# auxDaqUnitTopDigital2022_-_2.net
KiCad netlist of a schematic drawn in EAGLE
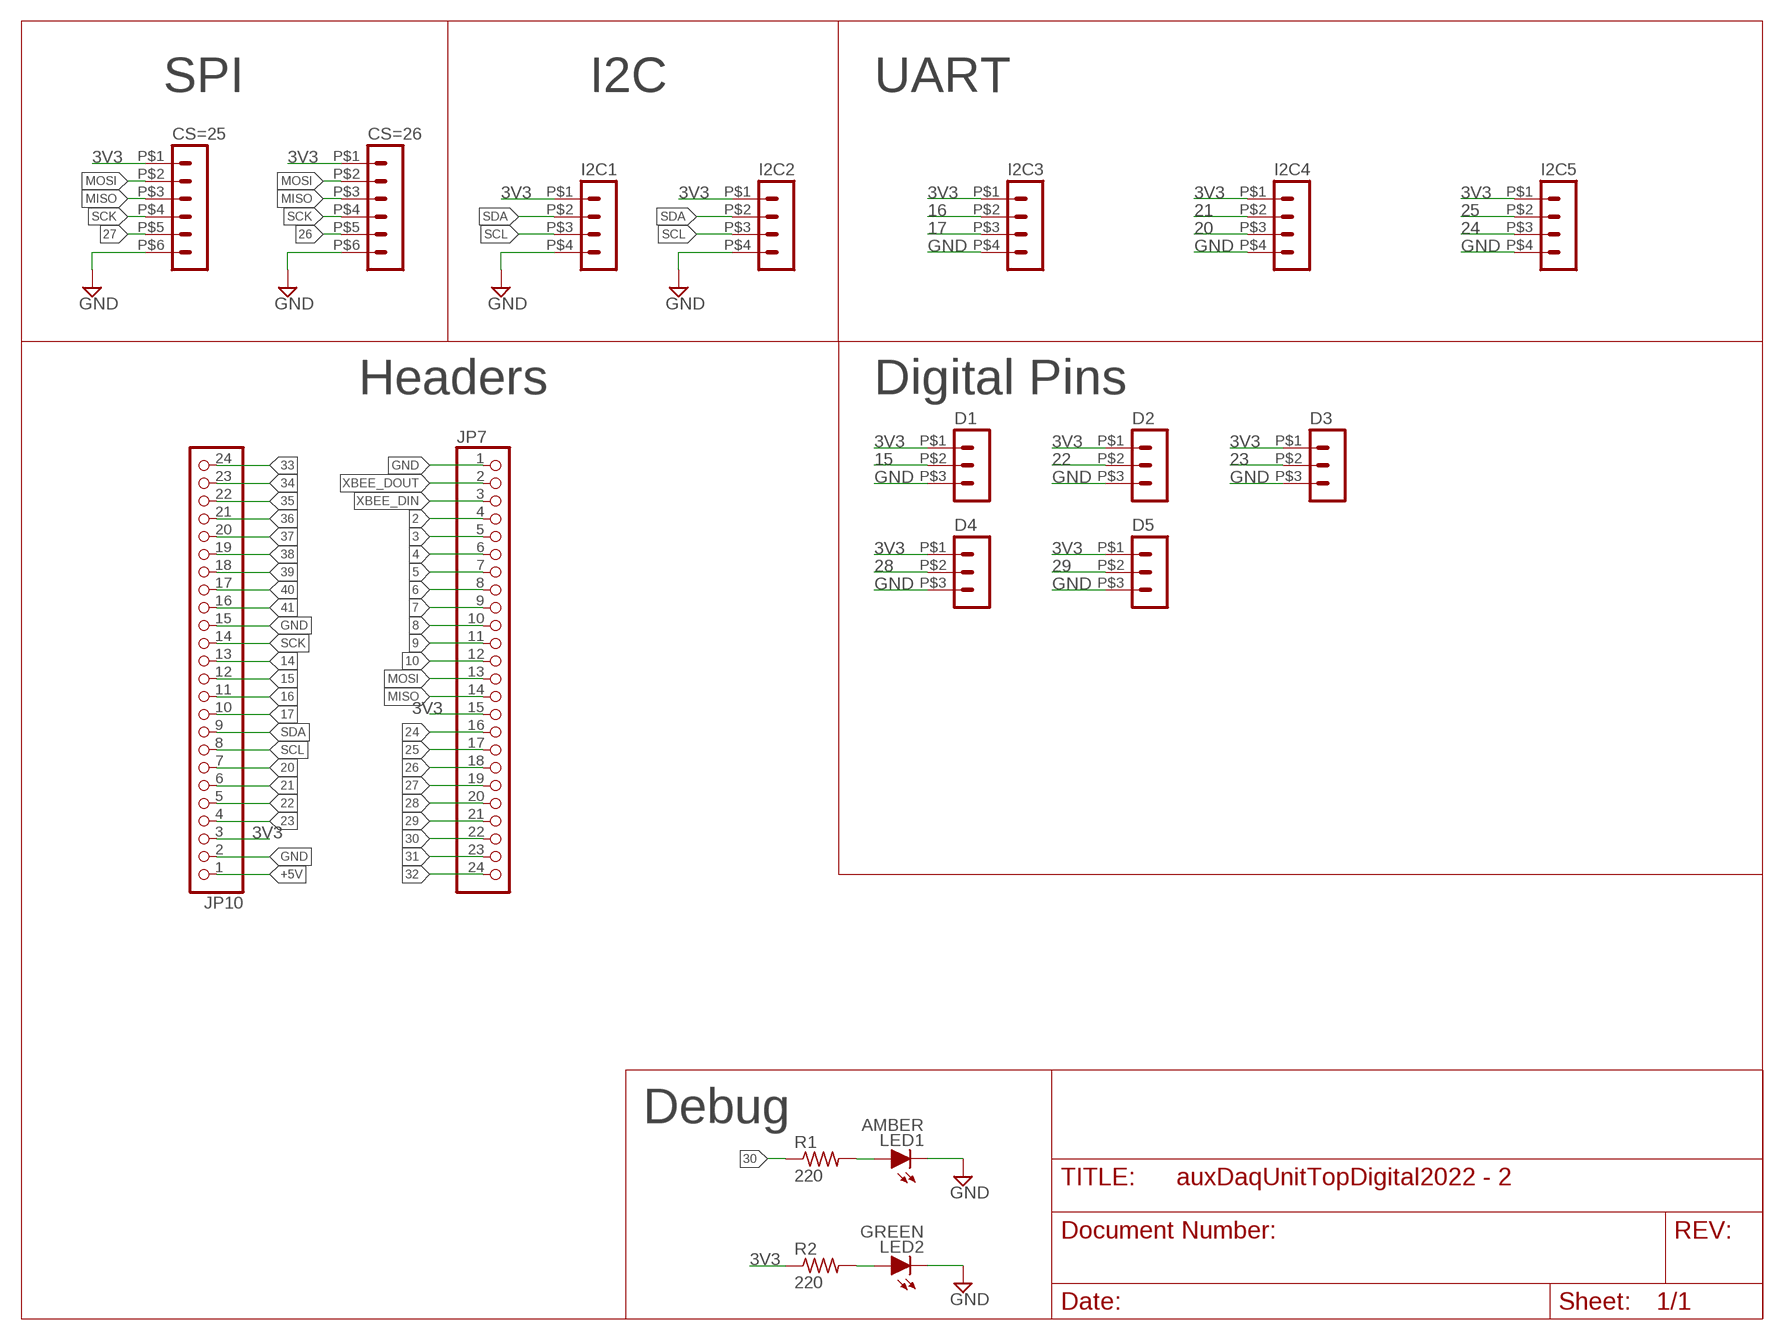
[diagram p0: schematic, sheet 1]

(export (version "E")
  (design (tool "Eeschema 10.0.6"))
  (components
    (comp (ref "CS=25")
      (value "HEADER_POS6_43045-0600")
      (footprint "eagle-import:43045-0600")
      (libsource (lib "eagle-import") (part "HEADER_POS6_?43045-0600"))
    )
    (comp (ref "CS=26")
      (value "HEADER_POS6_43045-0600")
      (footprint "eagle-import:43045-0600")
      (libsource (lib "eagle-import") (part "HEADER_POS6_?43045-0600"))
    )
    (comp (ref "D1")
      (value "HEADER_POS3_43650-0300")
      (footprint "eagle-import:43650-0300")
      (libsource (lib "eagle-import") (part "HEADER_POS3_?43650-0300"))
    )
    (comp (ref "D2")
      (value "HEADER_POS3_43650-0300")
      (footprint "eagle-import:43650-0300")
      (libsource (lib "eagle-import") (part "HEADER_POS3_?43650-0300"))
    )
    (comp (ref "D3")
      (value "HEADER_POS3_43650-0300")
      (footprint "eagle-import:43650-0300")
      (libsource (lib "eagle-import") (part "HEADER_POS3_?43650-0300"))
    )
    (comp (ref "D4")
      (value "HEADER_POS3_43650-0300")
      (footprint "eagle-import:43650-0300")
      (libsource (lib "eagle-import") (part "HEADER_POS3_?43650-0300"))
    )
    (comp (ref "D5")
      (value "HEADER_POS3_43650-0300")
      (footprint "eagle-import:43650-0300")
      (libsource (lib "eagle-import") (part "HEADER_POS3_?43650-0300"))
    )
    (comp (ref "I2C1")
      (value "HEADER_POS4_43045-0401")
      (footprint "eagle-import:43045-0400")
      (libsource (lib "eagle-import") (part "HEADER_POS4_?43045-0401"))
    )
    (comp (ref "I2C2")
      (value "HEADER_POS4_43045-0401")
      (footprint "eagle-import:43045-0400")
      (libsource (lib "eagle-import") (part "HEADER_POS4_?43045-0401"))
    )
    (comp (ref "I2C3")
      (value "HEADER_POS4_43045-0401")
      (footprint "eagle-import:43045-0400")
      (libsource (lib "eagle-import") (part "HEADER_POS4_?43045-0401"))
    )
    (comp (ref "I2C4")
      (value "HEADER_POS4_43045-0401")
      (footprint "eagle-import:43045-0400")
      (libsource (lib "eagle-import") (part "HEADER_POS4_?43045-0401"))
    )
    (comp (ref "I2C5")
      (value "HEADER_POS4_43045-0401")
      (footprint "eagle-import:43045-0400")
      (libsource (lib "eagle-import") (part "HEADER_POS4_?43045-0401"))
    )
    (comp (ref "JP7")
      (value "PINHD-1X24")
      (footprint "eagle-import:1X24")
      (libsource (lib "eagle-import") (part "PINHD-1X24"))
    )
    (comp (ref "JP10")
      (value "PINHD-1X24")
      (footprint "eagle-import:1X24")
      (libsource (lib "eagle-import") (part "PINHD-1X24"))
    )
    (comp (ref "LED1")
      (value "AMBER")
      (footprint "eagle-import:LED-603")
      (libsource (lib "eagle-import") (part "LED-0603"))
    )
    (comp (ref "LED2")
      (value "GREEN")
      (footprint "eagle-import:LED-603")
      (libsource (lib "eagle-import") (part "LED-0603"))
    )
    (comp (ref "R1")
      (value "220")
      (footprint "eagle-import:R0603")
      (libsource (lib "eagle-import") (part "RES_SMDR0603"))
    )
    (comp (ref "R2")
      (value "220")
      (footprint "eagle-import:R0603")
      (libsource (lib "eagle-import") (part "RES_SMDR0603"))
    )
  )
  (nets
    (net (code "1") (name "+5V") (class "Default")
      (node (ref "JP10") (pin "1") (pinfunction "1_1") (pintype "passive"))
    )
    (net (code "2") (name "/3V3") (class "Default")
      (node (ref "CS=25") (pin "P$1") (pinfunction "1_P$1") (pintype "passive"))
      (node (ref "CS=26") (pin "P$1") (pinfunction "1_P$1") (pintype "passive"))
      (node (ref "D1") (pin "P$1") (pinfunction "1_P$1") (pintype "passive"))
      (node (ref "D2") (pin "P$1") (pinfunction "1_P$1") (pintype "passive"))
      (node (ref "D3") (pin "P$1") (pinfunction "1_P$1") (pintype "passive"))
      (node (ref "D4") (pin "P$1") (pinfunction "1_P$1") (pintype "passive"))
      (node (ref "D5") (pin "P$1") (pinfunction "1_P$1") (pintype "passive"))
      (node (ref "I2C1") (pin "P$1") (pinfunction "1_P$1") (pintype "passive"))
      (node (ref "I2C2") (pin "P$1") (pinfunction "1_P$1") (pintype "passive"))
      (node (ref "I2C3") (pin "P$1") (pinfunction "1_P$1") (pintype "passive"))
      (node (ref "I2C4") (pin "P$1") (pinfunction "1_P$1") (pintype "passive"))
      (node (ref "I2C5") (pin "P$1") (pinfunction "1_P$1") (pintype "passive"))
      (node (ref "JP10") (pin "3") (pinfunction "3_3") (pintype "passive"))
      (node (ref "JP7") (pin "15") (pinfunction "15_15") (pintype "passive"))
      (node (ref "R2") (pin "1") (pinfunction "1_1") (pintype "passive"))
    )
    (net (code "3") (name "2") (class "Default")
      (node (ref "JP7") (pin "4") (pinfunction "4_4") (pintype "passive"))
    )
    (net (code "4") (name "3") (class "Default")
      (node (ref "JP7") (pin "5") (pinfunction "5_5") (pintype "passive"))
    )
    (net (code "5") (name "4") (class "Default")
      (node (ref "JP7") (pin "6") (pinfunction "6_6") (pintype "passive"))
    )
    (net (code "6") (name "5") (class "Default")
      (node (ref "JP7") (pin "7") (pinfunction "7_7") (pintype "passive"))
    )
    (net (code "7") (name "6") (class "Default")
      (node (ref "JP7") (pin "8") (pinfunction "8_8") (pintype "passive"))
    )
    (net (code "8") (name "7") (class "Default")
      (node (ref "JP7") (pin "9") (pinfunction "9_9") (pintype "passive"))
    )
    (net (code "9") (name "8") (class "Default")
      (node (ref "JP7") (pin "10") (pinfunction "10_10") (pintype "passive"))
    )
    (net (code "10") (name "9") (class "Default")
      (node (ref "JP7") (pin "11") (pinfunction "11_11") (pintype "passive"))
    )
    (net (code "11") (name "10") (class "Default")
      (node (ref "JP7") (pin "12") (pinfunction "12_12") (pintype "passive"))
    )
    (net (code "12") (name "14") (class "Default")
      (node (ref "JP10") (pin "13") (pinfunction "13_13") (pintype "passive"))
    )
    (net (code "13") (name "15") (class "Default")
      (node (ref "D1") (pin "P$2") (pinfunction "2_P$2") (pintype "passive"))
      (node (ref "JP10") (pin "12") (pinfunction "12_12") (pintype "passive"))
    )
    (net (code "14") (name "16") (class "Default")
      (node (ref "I2C3") (pin "P$2") (pinfunction "2_P$2") (pintype "passive"))
      (node (ref "JP10") (pin "11") (pinfunction "11_11") (pintype "passive"))
    )
    (net (code "15") (name "17") (class "Default")
      (node (ref "I2C3") (pin "P$3") (pinfunction "3_P$3") (pintype "passive"))
      (node (ref "JP10") (pin "10") (pinfunction "10_10") (pintype "passive"))
    )
    (net (code "16") (name "20") (class "Default")
      (node (ref "I2C4") (pin "P$3") (pinfunction "3_P$3") (pintype "passive"))
      (node (ref "JP10") (pin "7") (pinfunction "7_7") (pintype "passive"))
    )
    (net (code "17") (name "21") (class "Default")
      (node (ref "I2C4") (pin "P$2") (pinfunction "2_P$2") (pintype "passive"))
      (node (ref "JP10") (pin "6") (pinfunction "6_6") (pintype "passive"))
    )
    (net (code "18") (name "22") (class "Default")
      (node (ref "D2") (pin "P$2") (pinfunction "2_P$2") (pintype "passive"))
      (node (ref "JP10") (pin "5") (pinfunction "5_5") (pintype "passive"))
    )
    (net (code "19") (name "23") (class "Default")
      (node (ref "D3") (pin "P$2") (pinfunction "2_P$2") (pintype "passive"))
      (node (ref "JP10") (pin "4") (pinfunction "4_4") (pintype "passive"))
    )
    (net (code "20") (name "24") (class "Default")
      (node (ref "I2C5") (pin "P$3") (pinfunction "3_P$3") (pintype "passive"))
      (node (ref "JP7") (pin "16") (pinfunction "16_16") (pintype "passive"))
    )
    (net (code "21") (name "25") (class "Default")
      (node (ref "I2C5") (pin "P$2") (pinfunction "2_P$2") (pintype "passive"))
      (node (ref "JP7") (pin "17") (pinfunction "17_17") (pintype "passive"))
    )
    (net (code "22") (name "26") (class "Default")
      (node (ref "CS=26") (pin "P$5") (pinfunction "5_P$5") (pintype "passive"))
      (node (ref "JP7") (pin "18") (pinfunction "18_18") (pintype "passive"))
    )
    (net (code "23") (name "27") (class "Default")
      (node (ref "CS=25") (pin "P$5") (pinfunction "5_P$5") (pintype "passive"))
      (node (ref "JP7") (pin "19") (pinfunction "19_19") (pintype "passive"))
    )
    (net (code "24") (name "28") (class "Default")
      (node (ref "D4") (pin "P$2") (pinfunction "2_P$2") (pintype "passive"))
      (node (ref "JP7") (pin "20") (pinfunction "20_20") (pintype "passive"))
    )
    (net (code "25") (name "29") (class "Default")
      (node (ref "D5") (pin "P$2") (pinfunction "2_P$2") (pintype "passive"))
      (node (ref "JP7") (pin "21") (pinfunction "21_21") (pintype "passive"))
    )
    (net (code "26") (name "30") (class "Default")
      (node (ref "JP7") (pin "22") (pinfunction "22_22") (pintype "passive"))
      (node (ref "R1") (pin "1") (pinfunction "1_1") (pintype "passive"))
    )
    (net (code "27") (name "31") (class "Default")
      (node (ref "JP7") (pin "23") (pinfunction "23_23") (pintype "passive"))
    )
    (net (code "28") (name "32") (class "Default")
      (node (ref "JP7") (pin "24") (pinfunction "24_24") (pintype "passive"))
    )
    (net (code "29") (name "33") (class "Default")
      (node (ref "JP10") (pin "24") (pinfunction "24_24") (pintype "passive"))
    )
    (net (code "30") (name "34") (class "Default")
      (node (ref "JP10") (pin "23") (pinfunction "23_23") (pintype "passive"))
    )
    (net (code "31") (name "35") (class "Default")
      (node (ref "JP10") (pin "22") (pinfunction "22_22") (pintype "passive"))
    )
    (net (code "32") (name "36") (class "Default")
      (node (ref "JP10") (pin "21") (pinfunction "21_21") (pintype "passive"))
    )
    (net (code "33") (name "37") (class "Default")
      (node (ref "JP10") (pin "20") (pinfunction "20_20") (pintype "passive"))
    )
    (net (code "34") (name "38") (class "Default")
      (node (ref "JP10") (pin "19") (pinfunction "19_19") (pintype "passive"))
    )
    (net (code "35") (name "39") (class "Default")
      (node (ref "JP10") (pin "18") (pinfunction "18_18") (pintype "passive"))
    )
    (net (code "36") (name "40") (class "Default")
      (node (ref "JP10") (pin "17") (pinfunction "17_17") (pintype "passive"))
    )
    (net (code "37") (name "41") (class "Default")
      (node (ref "JP10") (pin "16") (pinfunction "16_16") (pintype "passive"))
    )
    (net (code "38") (name "GND") (class "Default")
      (node (ref "CS=25") (pin "P$6") (pinfunction "6_P$6") (pintype "passive"))
      (node (ref "CS=26") (pin "P$6") (pinfunction "6_P$6") (pintype "passive"))
      (node (ref "D1") (pin "P$3") (pinfunction "3_P$3") (pintype "passive"))
      (node (ref "D2") (pin "P$3") (pinfunction "3_P$3") (pintype "passive"))
      (node (ref "D3") (pin "P$3") (pinfunction "3_P$3") (pintype "passive"))
      (node (ref "D4") (pin "P$3") (pinfunction "3_P$3") (pintype "passive"))
      (node (ref "D5") (pin "P$3") (pinfunction "3_P$3") (pintype "passive"))
      (node (ref "I2C1") (pin "P$4") (pinfunction "4_P$4") (pintype "passive"))
      (node (ref "I2C2") (pin "P$4") (pinfunction "4_P$4") (pintype "passive"))
      (node (ref "I2C3") (pin "P$4") (pinfunction "4_P$4") (pintype "passive"))
      (node (ref "I2C4") (pin "P$4") (pinfunction "4_P$4") (pintype "passive"))
      (node (ref "I2C5") (pin "P$4") (pinfunction "4_P$4") (pintype "passive"))
      (node (ref "JP10") (pin "15") (pinfunction "15_15") (pintype "passive"))
      (node (ref "JP10") (pin "2") (pinfunction "2_2") (pintype "passive"))
      (node (ref "JP7") (pin "1") (pinfunction "1_1") (pintype "passive"))
      (node (ref "LED1") (pin "C") (pinfunction "C_C") (pintype "passive"))
      (node (ref "LED2") (pin "C") (pinfunction "C_C") (pintype "passive"))
    )
    (net (code "39") (name "MISO") (class "Default")
      (node (ref "CS=25") (pin "P$3") (pinfunction "3_P$3") (pintype "passive"))
      (node (ref "CS=26") (pin "P$3") (pinfunction "3_P$3") (pintype "passive"))
      (node (ref "JP7") (pin "14") (pinfunction "14_14") (pintype "passive"))
    )
    (net (code "40") (name "MOSI") (class "Default")
      (node (ref "CS=25") (pin "P$2") (pinfunction "2_P$2") (pintype "passive"))
      (node (ref "CS=26") (pin "P$2") (pinfunction "2_P$2") (pintype "passive"))
      (node (ref "JP7") (pin "13") (pinfunction "13_13") (pintype "passive"))
    )
    (net (code "41") (name "Net-(LED1-PadA)") (class "Default")
      (node (ref "LED1") (pin "A") (pinfunction "A_A") (pintype "passive"))
      (node (ref "R1") (pin "2") (pinfunction "2_2") (pintype "passive"))
    )
    (net (code "42") (name "Net-(LED2-PadA)") (class "Default")
      (node (ref "LED2") (pin "A") (pinfunction "A_A") (pintype "passive"))
      (node (ref "R2") (pin "2") (pinfunction "2_2") (pintype "passive"))
    )
    (net (code "43") (name "SCK") (class "Default")
      (node (ref "CS=25") (pin "P$4") (pinfunction "4_P$4") (pintype "passive"))
      (node (ref "CS=26") (pin "P$4") (pinfunction "4_P$4") (pintype "passive"))
      (node (ref "JP10") (pin "14") (pinfunction "14_14") (pintype "passive"))
    )
    (net (code "44") (name "SCL") (class "Default")
      (node (ref "I2C1") (pin "P$3") (pinfunction "3_P$3") (pintype "passive"))
      (node (ref "I2C2") (pin "P$3") (pinfunction "3_P$3") (pintype "passive"))
      (node (ref "JP10") (pin "8") (pinfunction "8_8") (pintype "passive"))
    )
    (net (code "45") (name "SDA") (class "Default")
      (node (ref "I2C1") (pin "P$2") (pinfunction "2_P$2") (pintype "passive"))
      (node (ref "I2C2") (pin "P$2") (pinfunction "2_P$2") (pintype "passive"))
      (node (ref "JP10") (pin "9") (pinfunction "9_9") (pintype "passive"))
    )
    (net (code "46") (name "XBEE_DIN") (class "Default")
      (node (ref "JP7") (pin "3") (pinfunction "3_3") (pintype "passive"))
    )
    (net (code "47") (name "XBEE_DOUT") (class "Default")
      (node (ref "JP7") (pin "2") (pinfunction "2_2") (pintype "passive"))
    )
  )
)
